# can_connector.net
KiCad netlist of a schematic drawn in Altium Designer
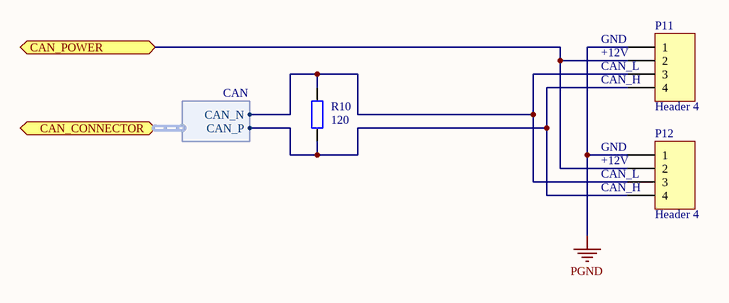
[diagram p0: can connector.SchDoc]

(export (version "E")
  (design (tool "Eeschema 10.0.6"))
  (components
    (comp (ref "P11")
      (value "Header 4")
      (footprint "B04B-PASK-1")
      (description "Header, 4-Pin")
      (fields (field (name "PUBLISHER") "Altium Limited"))
      (libsource (lib "Miscellaneous Connectors") (part "Header 4"))
    )
    (comp (ref "P12")
      (value "Header 4")
      (footprint "B04B-PASK-1")
      (description "Header, 4-Pin")
      (fields (field (name "PUBLISHER") "Altium Limited"))
      (libsource (lib "Miscellaneous Connectors") (part "Header 4"))
    )
    (comp (ref "R10")
      (value "120")
      (footprint "R0603")
      (description "Resistor")
      (fields (field (name "Comment") "Res2") (field (name "PUBLISHER") "Altium Limited"))
      (libsource (lib "Miscellaneous Devices") (part "Res2"))
    )
  )
  (nets
    (net (code "2") (name "/CAN_POWER") (class "Default")
      (node (ref "P11") (pin "2") (pinfunction "2_2") (pintype "passive"))
      (node (ref "P12") (pin "2") (pinfunction "2_2") (pintype "passive"))
    )
    (net (code "4") (name "Net-(P11-Pad3)") (class "Default")
      (node (ref "P11") (pin "3") (pinfunction "3_3") (pintype "passive"))
      (node (ref "P12") (pin "3") (pinfunction "3_3") (pintype "passive"))
      (node (ref "R10") (pin "2") (pinfunction "2_2") (pintype "passive"))
    )
    (net (code "5") (name "Net-(P11-Pad4)") (class "Default")
      (node (ref "P11") (pin "4") (pinfunction "4_4") (pintype "passive"))
      (node (ref "P12") (pin "4") (pinfunction "4_4") (pintype "passive"))
      (node (ref "R10") (pin "1") (pinfunction "1_1") (pintype "passive"))
    )
    (net (code "6") (name "PGND") (class "Default")
      (node (ref "P11") (pin "1") (pinfunction "1_1") (pintype "passive"))
      (node (ref "P12") (pin "1") (pinfunction "1_1") (pintype "passive"))
    )
  )
)
